# WKDoubleTXG0.net
KiCad netlist of a schematic drawn in EasyEDA Pro
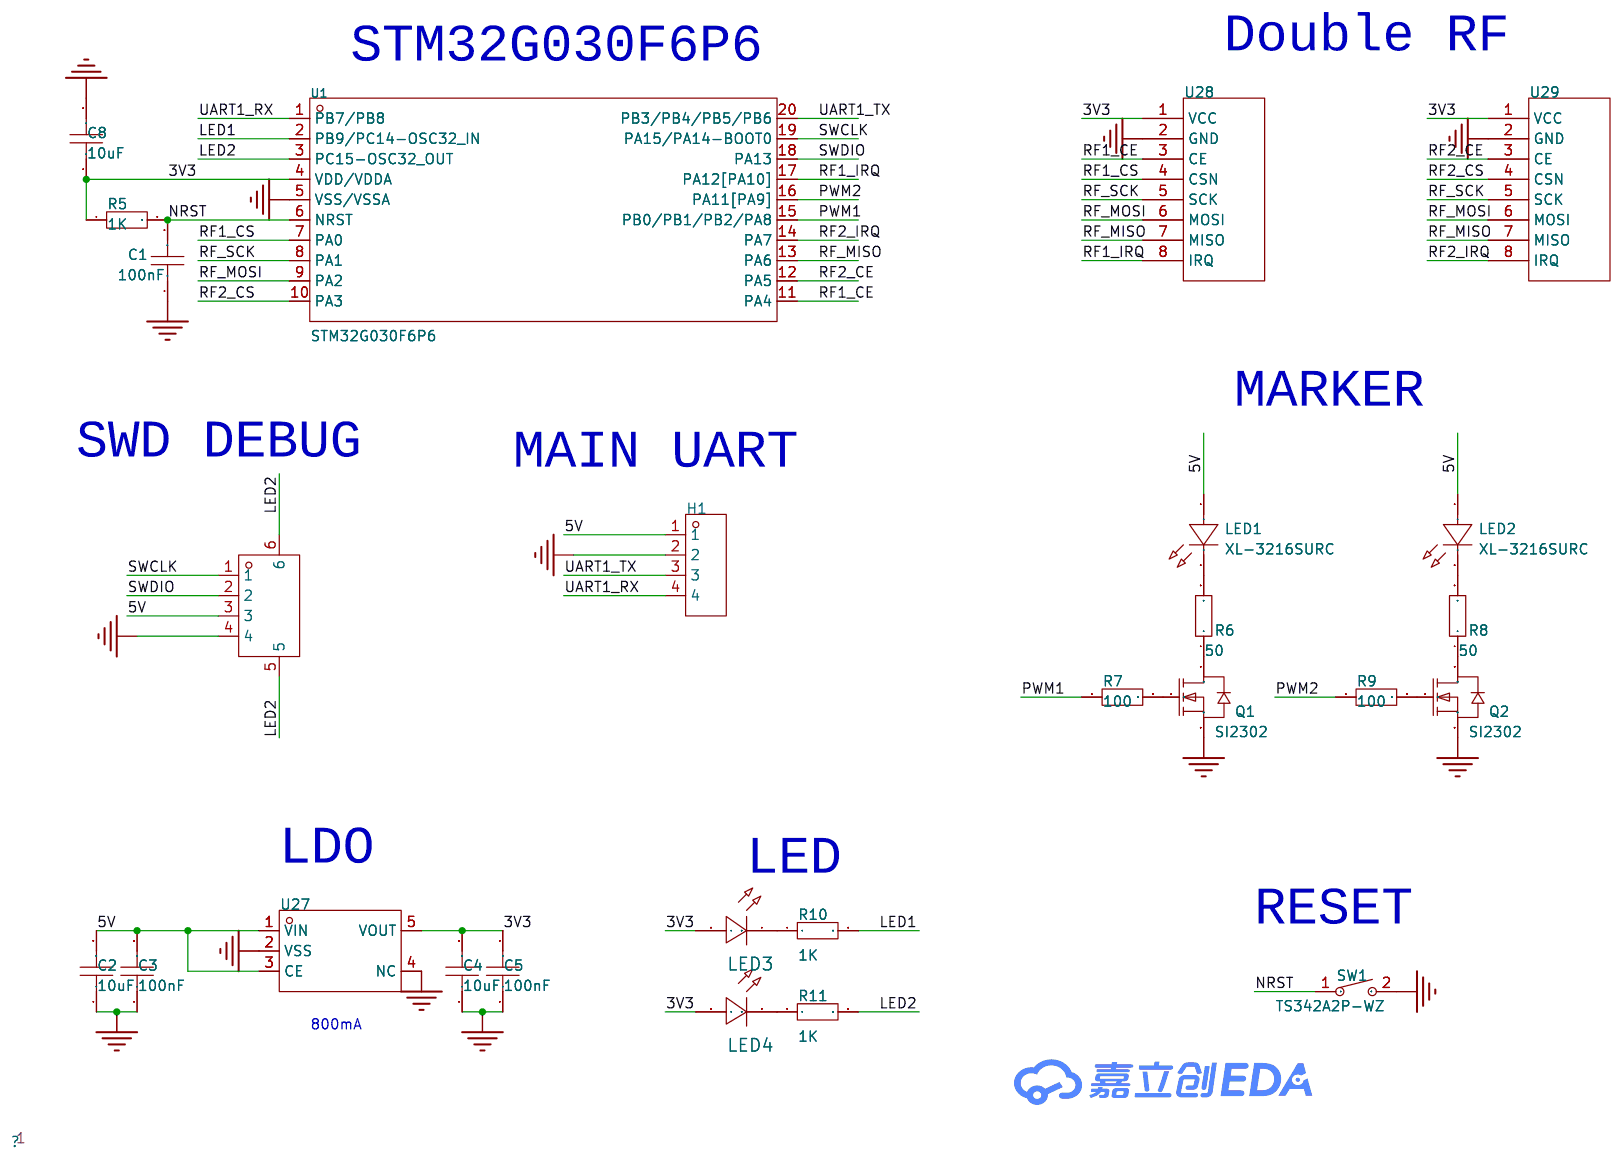
[diagram p0: schematic sheet]

(export (version "E")
  (design (tool "Eeschema 10.0.6"))
  (components
    (comp (ref "C1")
      (value "100nF")
      (footprint "easyedapro:C0603")
      (libsource (lib "easyedapro") (part "CapAcitance"))
    )
    (comp (ref "C2")
      (value "10uF")
      (footprint "easyedapro:C0603")
      (libsource (lib "easyedapro") (part "CapAcitance"))
    )
    (comp (ref "C3")
      (value "100nF")
      (footprint "easyedapro:C0603")
      (libsource (lib "easyedapro") (part "CapAcitance"))
    )
    (comp (ref "C4")
      (value "10uF")
      (footprint "easyedapro:C0603")
      (libsource (lib "easyedapro") (part "CapAcitance"))
    )
    (comp (ref "C5")
      (value "100nF")
      (footprint "easyedapro:C0603")
      (libsource (lib "easyedapro") (part "CapAcitance"))
    )
    (comp (ref "C8")
      (value "10uF")
      (footprint "easyedapro:C0603")
      (libsource (lib "easyedapro") (part "CapAcitance"))
    )
    (comp (ref "H1")
      (value "~")
      (footprint "easyedapro:HDR-TH_4P-P2.54-V-F")
      (libsource (lib "easyedapro") (part "2.54-1*4P母"))
    )
    (comp (ref "LED1")
      (value "XL-3216SURC")
      (footprint "easyedapro:LED1206-R-RD_RED")
      (description "发光颜色:红色;功率:55mW;正向电流:25mA;主波长:617nm~621nm;透镜颜色:无色透明透镜;色温:-;发光角度:120°;载带方式:正贴;工作温度:-30°C~+85°C;")
      (fields (field (name "Manufacturer") "XINGLIGHT(成兴光)"))
      (libsource (lib "easyedapro") (part "XL-3216SURC"))
    )
    (comp (ref "LED2")
      (value "XL-3216SURC")
      (footprint "easyedapro:LED1206-R-RD_RED")
      (description "发光颜色:红色;功率:55mW;正向电流:25mA;主波长:617nm~621nm;透镜颜色:无色透明透镜;色温:-;发光角度:120°;载带方式:正贴;工作温度:-30°C~+85°C;")
      (fields (field (name "Manufacturer") "XINGLIGHT(成兴光)"))
      (libsource (lib "easyedapro") (part "XL-3216SURC"))
    )
    (comp (ref "LED3")
      (value "~")
      (footprint "easyedapro:LED_0603")
      (libsource (lib "easyedapro") (part "LED_R"))
    )
    (comp (ref "LED4")
      (value "~")
      (footprint "easyedapro:LED_0603")
      (libsource (lib "easyedapro") (part "LED_R"))
    )
    (comp (ref "Q1")
      (value "SI2302")
      (footprint "easyedapro:SOT-23-3_L2.9-W1.3-P1.90-LS2.4-BR")
      (fields (field (name "Manufacturer") "TECH PUBLIC(台舟)"))
      (libsource (lib "easyedapro") (part "SI2302_C2841377"))
    )
    (comp (ref "Q2")
      (value "SI2302")
      (footprint "easyedapro:SOT-23-3_L2.9-W1.3-P1.90-LS2.4-BR")
      (fields (field (name "Manufacturer") "TECH PUBLIC(台舟)"))
      (libsource (lib "easyedapro") (part "SI2302_C2841377"))
    )
    (comp (ref "R5") (value "1K") (footprint "easyedapro:R0603") (libsource (lib "easyedapro") (part "电阻")))
    (comp (ref "R6") (value "50") (footprint "easyedapro:R0603") (libsource (lib "easyedapro") (part "电阻")))
    (comp (ref "R7") (value "100") (footprint "easyedapro:R0603") (libsource (lib "easyedapro") (part "电阻")))
    (comp (ref "R8") (value "50") (footprint "easyedapro:R0603") (libsource (lib "easyedapro") (part "电阻")))
    (comp (ref "R9") (value "100") (footprint "easyedapro:R0603") (libsource (lib "easyedapro") (part "电阻")))
    (comp (ref "R10") (value "1K") (footprint "easyedapro:R0603") (libsource (lib "easyedapro") (part "电阻")))
    (comp (ref "R11") (value "1K") (footprint "easyedapro:R0603") (libsource (lib "easyedapro") (part "电阻")))
    (comp (ref "SW1")
      (value "TS342A2P-WZ")
      (footprint "easyedapro:SW-SMD_L4.0-W2.9-LS5.0")
      (fields (field (name "Manufacturer") "SHOU HAN(首韩)"))
      (libsource (lib "easyedapro") (part "TS342A2P-WZ"))
    )
    (comp (ref "U1")
      (value "STM32G030F6P6")
      (footprint "easyedapro:TSSOP-20_L6.5-W4.4-P0.65-LS6.4-BL")
      (description "CPU内核:CM0;程序存储容量:32KB;RAM总容量:8KB;GPIO端口数量:18;工作电压范围:2V~3.6V;CPU最大主频:64MHz;程序存储器类型:FLASH;")
      (fields (field (name "Manufacturer") "ST(意法半导体)"))
      (libsource (lib "easyedapro") (part "STM32G030F6P6"))
    )
    (comp (ref "U27")
      (value "ME6217C33M5G")
      (footprint "easyedapro:SOT-23-5_L3.0-W1.7-P0.95-LS2.8-BR")
      (description "输出类型:固定;输出极性:正;最大输入电压:7V;输出电压:3.3V;输出电流:800mA;电源纹波抑制比(PSRR):65dB@(1kHz);")
      (fields (field (name "Manufacturer") "MICRONE(南京微盟)"))
      (libsource (lib "easyedapro") (part "ME6217C33M5G"))
    )
    (comp (ref "U28")
      (value "~")
      (footprint "easyedapro:NF-03 SI24R1")
      (libsource (lib "easyedapro") (part "NF-03 SI24R1"))
    )
    (comp (ref "U29")
      (value "~")
      (footprint "easyedapro:NF-03 SI24R1")
      (libsource (lib "easyedapro") (part "NF-03 SI24R1"))
    )
    (comp (ref "U41")
      (value "ZX-SH1.0-4PWT")
      (footprint "easyedapro:CONN-SMD_4P-P1.00_MEGASTAR_ZX-SH1.0-4PWT")
      (description "插针结构:1x4P;间距:1mm;安装方式:卧贴;参考系列:SH;总PIN数:4P;排数:1;每排PIN数:4;行距:-;额定电流:-;触头材质:黄铜;触头镀层:锡;工作温度范围:-;")
      (fields (field (name "Manufacturer") "Megastar(兆星)"))
      (libsource (lib "easyedapro") (part "ZX-SH1.0-4PWT"))
    )
  )
  (nets
    (net (code "1") (name "/3V3") (class "Default")
      (node (ref "C4") (pin "2") (pinfunction "2_2") (pintype "input"))
      (node (ref "C5") (pin "2") (pinfunction "2_2") (pintype "input"))
      (node (ref "C8") (pin "1") (pinfunction "1_1") (pintype "input"))
      (node (ref "LED3") (pin "2") (pinfunction "A_2") (pintype "input"))
      (node (ref "LED4") (pin "2") (pinfunction "A_2") (pintype "input"))
      (node (ref "R5") (pin "1") (pinfunction "1_1") (pintype "input"))
      (node (ref "U1") (pin "4") (pinfunction "VDD/VDDA_4") (pintype "input"))
      (node (ref "U27") (pin "5") (pinfunction "VOUT_5") (pintype "input"))
      (node (ref "U28") (pin "1") (pinfunction "VCC_1") (pintype "input"))
      (node (ref "U29") (pin "1") (pinfunction "VCC_1") (pintype "input"))
    )
    (net (code "2") (name "/5V") (class "Default")
      (node (ref "C2") (pin "2") (pinfunction "2_2") (pintype "input"))
      (node (ref "C3") (pin "2") (pinfunction "2_2") (pintype "input"))
      (node (ref "H1") (pin "1") (pinfunction "1_1") (pintype "unspecified"))
      (node (ref "LED1") (pin "1") (pinfunction "K_1") (pintype "unspecified"))
      (node (ref "LED2") (pin "1") (pinfunction "K_1") (pintype "unspecified"))
      (node (ref "U27") (pin "1") (pinfunction "VIN_1") (pintype "input"))
      (node (ref "U27") (pin "3") (pinfunction "CE_3") (pintype "input"))
      (node (ref "U41") (pin "3") (pinfunction "3_3") (pintype "unspecified"))
    )
    (net (code "3") (name "/LED1") (class "Default")
      (node (ref "R10") (pin "2") (pinfunction "2_2") (pintype "input"))
      (node (ref "U1") (pin "2") (pinfunction "PB9/PC14-OSC32_IN_2") (pintype "input"))
    )
    (net (code "4") (name "/LED2") (class "Default")
      (node (ref "R11") (pin "2") (pinfunction "2_2") (pintype "input"))
      (node (ref "U1") (pin "3") (pinfunction "PC15-OSC32_OUT_3") (pintype "input"))
      (node (ref "U41") (pin "5") (pinfunction "5_5") (pintype "unspecified"))
      (node (ref "U41") (pin "6") (pinfunction "6_6") (pintype "unspecified"))
    )
    (net (code "5") (name "/NRST") (class "Default")
      (node (ref "C1") (pin "2") (pinfunction "2_2") (pintype "input"))
      (node (ref "R5") (pin "2") (pinfunction "2_2") (pintype "input"))
      (node (ref "SW1") (pin "1") (pinfunction "1_1") (pintype "unspecified"))
      (node (ref "U1") (pin "6") (pinfunction "NRST_6") (pintype "input"))
    )
    (net (code "6") (name "/PWM1") (class "Default")
      (node (ref "R7") (pin "1") (pinfunction "1_1") (pintype "input"))
      (node (ref "U1") (pin "15") (pinfunction "PB0/PB1/PB2/PA8_15") (pintype "input"))
    )
    (net (code "7") (name "/PWM2") (class "Default")
      (node (ref "R9") (pin "1") (pinfunction "1_1") (pintype "input"))
      (node (ref "U1") (pin "16") (pinfunction "PA11[PA9]_16") (pintype "input"))
    )
    (net (code "8") (name "/RF1_CE") (class "Default")
      (node (ref "U1") (pin "11") (pinfunction "PA4_11") (pintype "input"))
      (node (ref "U28") (pin "3") (pinfunction "CE_3") (pintype "input"))
    )
    (net (code "9") (name "/RF1_CS") (class "Default")
      (node (ref "U1") (pin "7") (pinfunction "PA0_7") (pintype "input"))
      (node (ref "U28") (pin "4") (pinfunction "CSN_4") (pintype "input"))
    )
    (net (code "10") (name "/RF1_IRQ") (class "Default")
      (node (ref "U1") (pin "17") (pinfunction "PA12[PA10]_17") (pintype "input"))
      (node (ref "U28") (pin "8") (pinfunction "IRQ_8") (pintype "input"))
    )
    (net (code "11") (name "/RF2_CE") (class "Default")
      (node (ref "U1") (pin "12") (pinfunction "PA5_12") (pintype "input"))
      (node (ref "U29") (pin "3") (pinfunction "CE_3") (pintype "input"))
    )
    (net (code "12") (name "/RF2_CS") (class "Default")
      (node (ref "U1") (pin "10") (pinfunction "PA3_10") (pintype "input"))
      (node (ref "U29") (pin "4") (pinfunction "CSN_4") (pintype "input"))
    )
    (net (code "13") (name "/RF2_IRQ") (class "Default")
      (node (ref "U1") (pin "14") (pinfunction "PA7_14") (pintype "input"))
      (node (ref "U29") (pin "8") (pinfunction "IRQ_8") (pintype "input"))
    )
    (net (code "14") (name "/RF_MISO") (class "Default")
      (node (ref "U1") (pin "13") (pinfunction "PA6_13") (pintype "input"))
      (node (ref "U28") (pin "7") (pinfunction "MISO_7") (pintype "input"))
      (node (ref "U29") (pin "7") (pinfunction "MISO_7") (pintype "input"))
    )
    (net (code "15") (name "/RF_MOSI") (class "Default")
      (node (ref "U1") (pin "9") (pinfunction "PA2_9") (pintype "input"))
      (node (ref "U28") (pin "6") (pinfunction "MOSI_6") (pintype "input"))
      (node (ref "U29") (pin "6") (pinfunction "MOSI_6") (pintype "input"))
    )
    (net (code "16") (name "/RF_SCK") (class "Default")
      (node (ref "U1") (pin "8") (pinfunction "PA1_8") (pintype "input"))
      (node (ref "U28") (pin "5") (pinfunction "SCK_5") (pintype "input"))
      (node (ref "U29") (pin "5") (pinfunction "SCK_5") (pintype "input"))
    )
    (net (code "17") (name "/SWCLK") (class "Default")
      (node (ref "U1") (pin "19") (pinfunction "PA15/PA14-BOOT0_19") (pintype "input"))
      (node (ref "U41") (pin "1") (pinfunction "1_1") (pintype "unspecified"))
    )
    (net (code "18") (name "/SWDIO") (class "Default")
      (node (ref "U1") (pin "18") (pinfunction "PA13_18") (pintype "input"))
      (node (ref "U41") (pin "2") (pinfunction "2_2") (pintype "unspecified"))
    )
    (net (code "19") (name "/UART1_RX") (class "Default")
      (node (ref "H1") (pin "4") (pinfunction "4_4") (pintype "unspecified"))
      (node (ref "U1") (pin "1") (pinfunction "PB7/PB8_1") (pintype "input"))
    )
    (net (code "20") (name "/UART1_TX") (class "Default")
      (node (ref "H1") (pin "3") (pinfunction "3_3") (pintype "unspecified"))
      (node (ref "U1") (pin "20") (pinfunction "PB3/PB4/PB5/PB6_20") (pintype "input"))
    )
    (net (code "21") (name "GND") (class "Default")
      (node (ref "C1") (pin "1") (pinfunction "1_1") (pintype "input"))
      (node (ref "C2") (pin "1") (pinfunction "1_1") (pintype "input"))
      (node (ref "C3") (pin "1") (pinfunction "1_1") (pintype "input"))
      (node (ref "C4") (pin "1") (pinfunction "1_1") (pintype "input"))
      (node (ref "C5") (pin "1") (pinfunction "1_1") (pintype "input"))
      (node (ref "C8") (pin "2") (pinfunction "2_2") (pintype "input"))
      (node (ref "H1") (pin "2") (pinfunction "2_2") (pintype "unspecified"))
      (node (ref "Q1") (pin "2") (pinfunction "S_2") (pintype "unspecified"))
      (node (ref "Q2") (pin "2") (pinfunction "S_2") (pintype "unspecified"))
      (node (ref "SW1") (pin "2") (pinfunction "2_2") (pintype "unspecified"))
      (node (ref "U1") (pin "5") (pinfunction "VSS/VSSA_5") (pintype "input"))
      (node (ref "U27") (pin "2") (pinfunction "VSS_2") (pintype "input"))
      (node (ref "U27") (pin "4") (pinfunction "NC_4") (pintype "input"))
      (node (ref "U28") (pin "2") (pinfunction "GND_2") (pintype "input"))
      (node (ref "U29") (pin "2") (pinfunction "GND_2") (pintype "input"))
      (node (ref "U41") (pin "4") (pinfunction "4_4") (pintype "unspecified"))
    )
    (net (code "22") (name "Net-(LED1-A)") (class "Default")
      (node (ref "LED1") (pin "2") (pinfunction "A_2") (pintype "unspecified"))
      (node (ref "R6") (pin "2") (pinfunction "2_2") (pintype "input"))
    )
    (net (code "23") (name "Net-(LED2-A)") (class "Default")
      (node (ref "LED2") (pin "2") (pinfunction "A_2") (pintype "unspecified"))
      (node (ref "R8") (pin "2") (pinfunction "2_2") (pintype "input"))
    )
    (net (code "24") (name "Net-(LED3-C)") (class "Default")
      (node (ref "LED3") (pin "1") (pinfunction "C_1") (pintype "input"))
      (node (ref "R10") (pin "1") (pinfunction "1_1") (pintype "input"))
    )
    (net (code "25") (name "Net-(LED4-C)") (class "Default")
      (node (ref "LED4") (pin "1") (pinfunction "C_1") (pintype "input"))
      (node (ref "R11") (pin "1") (pinfunction "1_1") (pintype "input"))
    )
    (net (code "26") (name "Net-(Q1-D)") (class "Default")
      (node (ref "Q1") (pin "3") (pinfunction "D_3") (pintype "unspecified"))
      (node (ref "R6") (pin "1") (pinfunction "1_1") (pintype "input"))
    )
    (net (code "27") (name "Net-(Q1-G)") (class "Default")
      (node (ref "Q1") (pin "1") (pinfunction "G_1") (pintype "unspecified"))
      (node (ref "R7") (pin "2") (pinfunction "2_2") (pintype "input"))
    )
    (net (code "28") (name "Net-(Q2-D)") (class "Default")
      (node (ref "Q2") (pin "3") (pinfunction "D_3") (pintype "unspecified"))
      (node (ref "R8") (pin "1") (pinfunction "1_1") (pintype "input"))
    )
    (net (code "29") (name "Net-(Q2-G)") (class "Default")
      (node (ref "Q2") (pin "1") (pinfunction "G_1") (pintype "unspecified"))
      (node (ref "R9") (pin "2") (pinfunction "2_2") (pintype "input"))
    )
  )
)
